# LPCB279_-_AND_GATES.net
KiCad netlist of a schematic drawn in Altium Designer
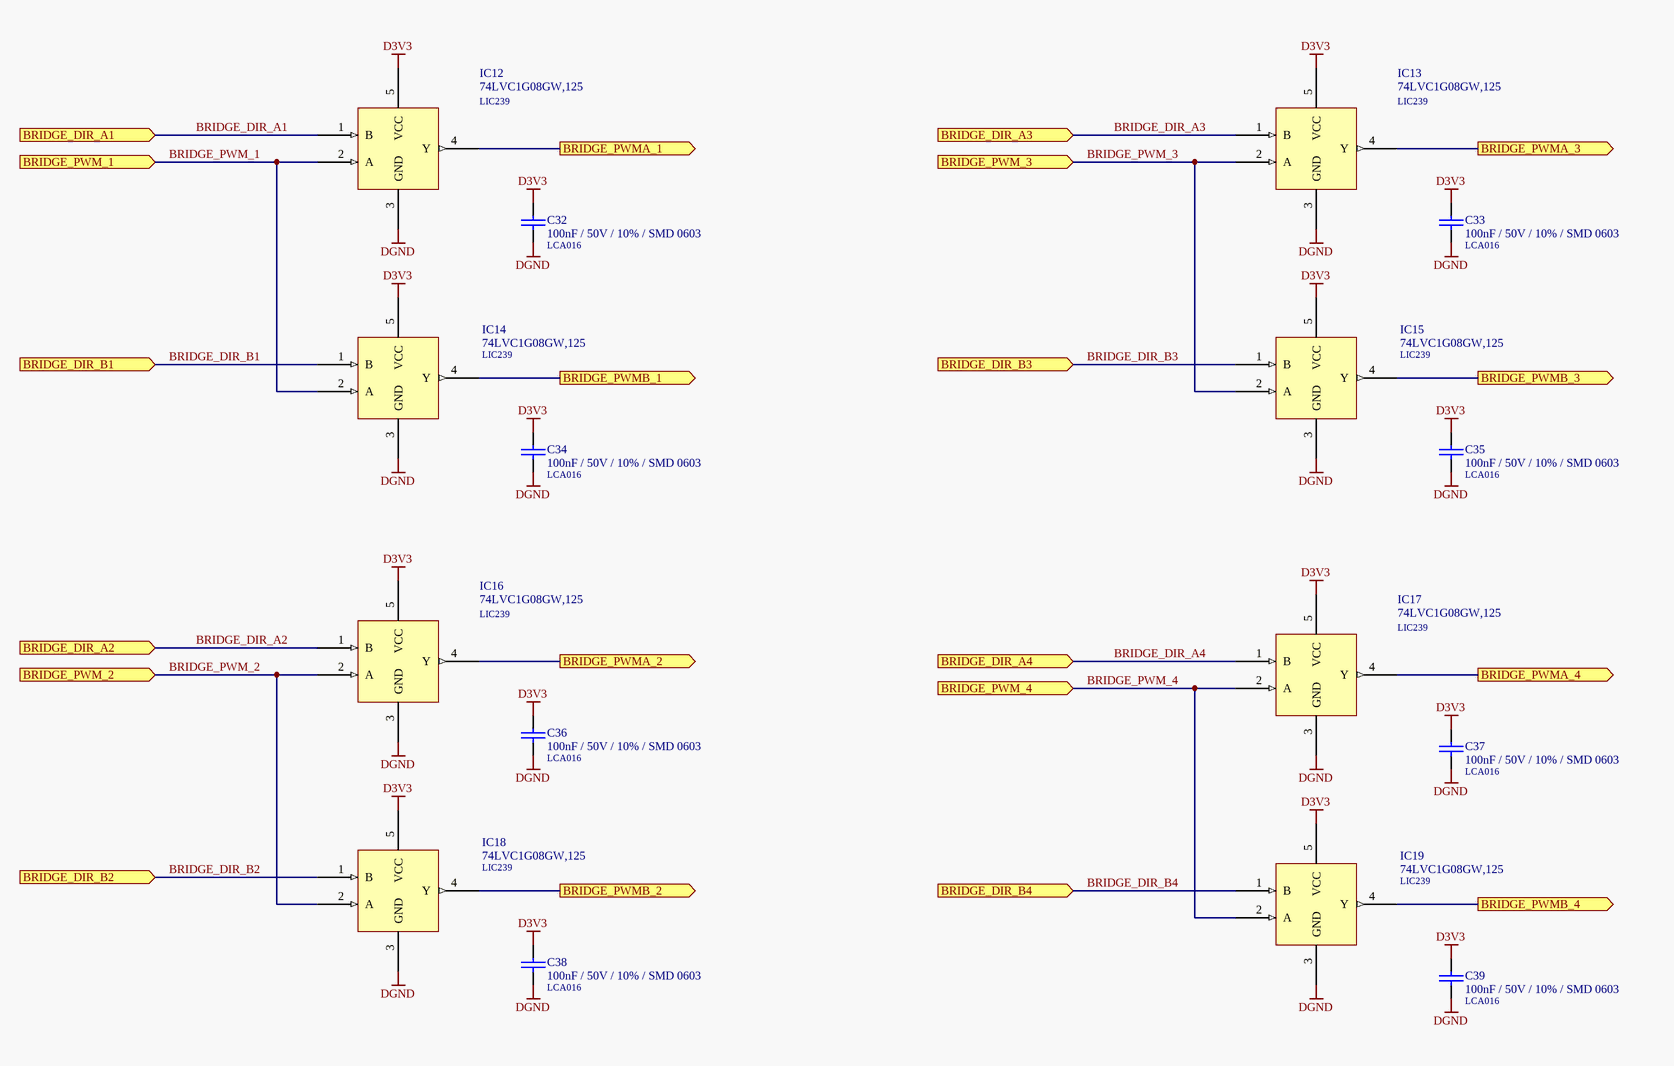
[diagram p0: LPCB279 - AND GATES.SchDoc]

(export (version "E")
  (design (tool "Eeschema 10.0.6"))
  (components
    (comp (ref "C32")
      (value "100nF / 50V / 10% / SMD 0603")
      (footprint "LFP011__CC1608-0603-IPC7351_B")
      (description "Capacitor, Ceramic Chip, 100nF (0.1uF), 50V, 5%, SMD 0603 [LCA016]")
      (fields (field (name "LDL_NUMBER") "LCA016"))
      (libsource (lib "LDL_Capacitors") (part "100nF / 50V / 10% / SMD 0603"))
    )
    (comp (ref "C33")
      (value "100nF / 50V / 10% / SMD 0603")
      (footprint "LFP011__CC1608-0603-IPC7351_B")
      (description "Capacitor, Ceramic Chip, 100nF (0.1uF), 50V, 5%, SMD 0603 [LCA016]")
      (fields (field (name "LDL_NUMBER") "LCA016"))
      (libsource (lib "LDL_Capacitors") (part "100nF / 50V / 10% / SMD 0603"))
    )
    (comp (ref "C34")
      (value "100nF / 50V / 10% / SMD 0603")
      (footprint "LFP011__CC1608-0603-IPC7351_B")
      (description "Capacitor, Ceramic Chip, 100nF (0.1uF), 50V, 5%, SMD 0603 [LCA016]")
      (fields (field (name "LDL_NUMBER") "LCA016"))
      (libsource (lib "LDL_Capacitors") (part "100nF / 50V / 10% / SMD 0603"))
    )
    (comp (ref "C35")
      (value "100nF / 50V / 10% / SMD 0603")
      (footprint "LFP011__CC1608-0603-IPC7351_B")
      (description "Capacitor, Ceramic Chip, 100nF (0.1uF), 50V, 5%, SMD 0603 [LCA016]")
      (fields (field (name "LDL_NUMBER") "LCA016"))
      (libsource (lib "LDL_Capacitors") (part "100nF / 50V / 10% / SMD 0603"))
    )
    (comp (ref "C36")
      (value "100nF / 50V / 10% / SMD 0603")
      (footprint "LFP011__CC1608-0603-IPC7351_B")
      (description "Capacitor, Ceramic Chip, 100nF (0.1uF), 50V, 5%, SMD 0603 [LCA016]")
      (fields (field (name "LDL_NUMBER") "LCA016"))
      (libsource (lib "LDL_Capacitors") (part "100nF / 50V / 10% / SMD 0603"))
    )
    (comp (ref "C37")
      (value "100nF / 50V / 10% / SMD 0603")
      (footprint "LFP011__CC1608-0603-IPC7351_B")
      (description "Capacitor, Ceramic Chip, 100nF (0.1uF), 50V, 5%, SMD 0603 [LCA016]")
      (fields (field (name "LDL_NUMBER") "LCA016"))
      (libsource (lib "LDL_Capacitors") (part "100nF / 50V / 10% / SMD 0603"))
    )
    (comp (ref "C38")
      (value "100nF / 50V / 10% / SMD 0603")
      (footprint "LFP011__CC1608-0603-IPC7351_B")
      (description "Capacitor, Ceramic Chip, 100nF (0.1uF), 50V, 5%, SMD 0603 [LCA016]")
      (fields (field (name "LDL_NUMBER") "LCA016"))
      (libsource (lib "LDL_Capacitors") (part "100nF / 50V / 10% / SMD 0603"))
    )
    (comp (ref "C39")
      (value "100nF / 50V / 10% / SMD 0603")
      (footprint "LFP011__CC1608-0603-IPC7351_B")
      (description "Capacitor, Ceramic Chip, 100nF (0.1uF), 50V, 5%, SMD 0603 [LCA016]")
      (fields (field (name "LDL_NUMBER") "LCA016"))
      (libsource (lib "LDL_Capacitors") (part "100nF / 50V / 10% / SMD 0603"))
    )
    (comp (ref "IC12")
      (value "74LVC1G08GW,125")
      (footprint "LFP047__SOT353")
      (description "IC, Logic AND Gate, Single 2 Input, SMD SOT353 [LIC239]")
      (fields (field (name "LDL_NUMBER") "LIC239"))
      (libsource (lib "LDL_Semiconductors") (part "74LVC1G08GW,125"))
    )
    (comp (ref "IC13")
      (value "74LVC1G08GW,125")
      (footprint "LFP047__SOT353")
      (description "IC, Logic AND Gate, Single 2 Input, SMD SOT353 [LIC239]")
      (fields (field (name "LDL_NUMBER") "LIC239"))
      (libsource (lib "LDL_Semiconductors") (part "74LVC1G08GW,125"))
    )
    (comp (ref "IC14")
      (value "74LVC1G08GW,125")
      (footprint "LFP047__SOT353")
      (description "IC, Logic AND Gate, Single 2 Input, SMD SOT353 [LIC239]")
      (fields (field (name "LDL_NUMBER") "LIC239"))
      (libsource (lib "LDL_Semiconductors") (part "74LVC1G08GW,125"))
    )
    (comp (ref "IC15")
      (value "74LVC1G08GW,125")
      (footprint "LFP047__SOT353")
      (description "IC, Logic AND Gate, Single 2 Input, SMD SOT353 [LIC239]")
      (fields (field (name "LDL_NUMBER") "LIC239"))
      (libsource (lib "LDL_Semiconductors") (part "74LVC1G08GW,125"))
    )
    (comp (ref "IC16")
      (value "74LVC1G08GW,125")
      (footprint "LFP047__SOT353")
      (description "IC, Logic AND Gate, Single 2 Input, SMD SOT353 [LIC239]")
      (fields (field (name "LDL_NUMBER") "LIC239"))
      (libsource (lib "LDL_Semiconductors") (part "74LVC1G08GW,125"))
    )
    (comp (ref "IC17")
      (value "74LVC1G08GW,125")
      (footprint "LFP047__SOT353")
      (description "IC, Logic AND Gate, Single 2 Input, SMD SOT353 [LIC239]")
      (fields (field (name "LDL_NUMBER") "LIC239"))
      (libsource (lib "LDL_Semiconductors") (part "74LVC1G08GW,125"))
    )
    (comp (ref "IC18")
      (value "74LVC1G08GW,125")
      (footprint "LFP047__SOT353")
      (description "IC, Logic AND Gate, Single 2 Input, SMD SOT353 [LIC239]")
      (fields (field (name "LDL_NUMBER") "LIC239"))
      (libsource (lib "LDL_Semiconductors") (part "74LVC1G08GW,125"))
    )
    (comp (ref "IC19")
      (value "74LVC1G08GW,125")
      (footprint "LFP047__SOT353")
      (description "IC, Logic AND Gate, Single 2 Input, SMD SOT353 [LIC239]")
      (fields (field (name "LDL_NUMBER") "LIC239"))
      (libsource (lib "LDL_Semiconductors") (part "74LVC1G08GW,125"))
    )
  )
  (nets
    (net (code "1") (name "/BRIDGE_DIR_A1") (class "Default")
      (node (ref "IC12") (pin "1") (pinfunction "B_1") (pintype "input"))
    )
    (net (code "2") (name "/BRIDGE_DIR_A2") (class "Default")
      (node (ref "IC16") (pin "1") (pinfunction "B_1") (pintype "input"))
    )
    (net (code "3") (name "/BRIDGE_DIR_A3") (class "Default")
      (node (ref "IC13") (pin "1") (pinfunction "B_1") (pintype "input"))
    )
    (net (code "4") (name "/BRIDGE_DIR_A4") (class "Default")
      (node (ref "IC17") (pin "1") (pinfunction "B_1") (pintype "input"))
    )
    (net (code "5") (name "/BRIDGE_DIR_B1") (class "Default")
      (node (ref "IC14") (pin "1") (pinfunction "B_1") (pintype "input"))
    )
    (net (code "6") (name "/BRIDGE_DIR_B2") (class "Default")
      (node (ref "IC18") (pin "1") (pinfunction "B_1") (pintype "input"))
    )
    (net (code "7") (name "/BRIDGE_DIR_B3") (class "Default")
      (node (ref "IC15") (pin "1") (pinfunction "B_1") (pintype "input"))
    )
    (net (code "8") (name "/BRIDGE_DIR_B4") (class "Default")
      (node (ref "IC19") (pin "1") (pinfunction "B_1") (pintype "input"))
    )
    (net (code "9") (name "/BRIDGE_PWMA_1") (class "Default")
      (node (ref "IC12") (pin "4") (pinfunction "Y_4") (pintype "output"))
    )
    (net (code "10") (name "/BRIDGE_PWMA_2") (class "Default")
      (node (ref "IC16") (pin "4") (pinfunction "Y_4") (pintype "output"))
    )
    (net (code "11") (name "/BRIDGE_PWMA_3") (class "Default")
      (node (ref "IC13") (pin "4") (pinfunction "Y_4") (pintype "output"))
    )
    (net (code "12") (name "/BRIDGE_PWMA_4") (class "Default")
      (node (ref "IC17") (pin "4") (pinfunction "Y_4") (pintype "output"))
    )
    (net (code "13") (name "/BRIDGE_PWMB_1") (class "Default")
      (node (ref "IC14") (pin "4") (pinfunction "Y_4") (pintype "output"))
    )
    (net (code "14") (name "/BRIDGE_PWMB_2") (class "Default")
      (node (ref "IC18") (pin "4") (pinfunction "Y_4") (pintype "output"))
    )
    (net (code "15") (name "/BRIDGE_PWMB_3") (class "Default")
      (node (ref "IC15") (pin "4") (pinfunction "Y_4") (pintype "output"))
    )
    (net (code "16") (name "/BRIDGE_PWMB_4") (class "Default")
      (node (ref "IC19") (pin "4") (pinfunction "Y_4") (pintype "output"))
    )
    (net (code "17") (name "/BRIDGE_PWM_1") (class "Default")
      (node (ref "IC12") (pin "2") (pinfunction "A_2") (pintype "input"))
      (node (ref "IC14") (pin "2") (pinfunction "A_2") (pintype "input"))
    )
    (net (code "18") (name "/BRIDGE_PWM_2") (class "Default")
      (node (ref "IC16") (pin "2") (pinfunction "A_2") (pintype "input"))
      (node (ref "IC18") (pin "2") (pinfunction "A_2") (pintype "input"))
    )
    (net (code "19") (name "/BRIDGE_PWM_3") (class "Default")
      (node (ref "IC13") (pin "2") (pinfunction "A_2") (pintype "input"))
      (node (ref "IC15") (pin "2") (pinfunction "A_2") (pintype "input"))
    )
    (net (code "20") (name "/BRIDGE_PWM_4") (class "Default")
      (node (ref "IC17") (pin "2") (pinfunction "A_2") (pintype "input"))
      (node (ref "IC19") (pin "2") (pinfunction "A_2") (pintype "input"))
    )
    (net (code "21") (name "D3V3") (class "Default")
      (node (ref "C32") (pin "1") (pintype "passive"))
      (node (ref "C33") (pin "1") (pintype "passive"))
      (node (ref "C34") (pin "1") (pintype "passive"))
      (node (ref "C35") (pin "1") (pintype "passive"))
      (node (ref "C36") (pin "1") (pintype "passive"))
      (node (ref "C37") (pin "1") (pintype "passive"))
      (node (ref "C38") (pin "1") (pintype "passive"))
      (node (ref "C39") (pin "1") (pintype "passive"))
      (node (ref "IC12") (pin "5") (pinfunction "VCC_5") (pintype "power_in"))
      (node (ref "IC13") (pin "5") (pinfunction "VCC_5") (pintype "power_in"))
      (node (ref "IC14") (pin "5") (pinfunction "VCC_5") (pintype "power_in"))
      (node (ref "IC15") (pin "5") (pinfunction "VCC_5") (pintype "power_in"))
      (node (ref "IC16") (pin "5") (pinfunction "VCC_5") (pintype "power_in"))
      (node (ref "IC17") (pin "5") (pinfunction "VCC_5") (pintype "power_in"))
      (node (ref "IC18") (pin "5") (pinfunction "VCC_5") (pintype "power_in"))
      (node (ref "IC19") (pin "5") (pinfunction "VCC_5") (pintype "power_in"))
    )
    (net (code "22") (name "DGND") (class "Default")
      (node (ref "C32") (pin "2") (pintype "passive"))
      (node (ref "C33") (pin "2") (pintype "passive"))
      (node (ref "C34") (pin "2") (pintype "passive"))
      (node (ref "C35") (pin "2") (pintype "passive"))
      (node (ref "C36") (pin "2") (pintype "passive"))
      (node (ref "C37") (pin "2") (pintype "passive"))
      (node (ref "C38") (pin "2") (pintype "passive"))
      (node (ref "C39") (pin "2") (pintype "passive"))
      (node (ref "IC12") (pin "3") (pinfunction "GND_3") (pintype "power_in"))
      (node (ref "IC13") (pin "3") (pinfunction "GND_3") (pintype "power_in"))
      (node (ref "IC14") (pin "3") (pinfunction "GND_3") (pintype "power_in"))
      (node (ref "IC15") (pin "3") (pinfunction "GND_3") (pintype "power_in"))
      (node (ref "IC16") (pin "3") (pinfunction "GND_3") (pintype "power_in"))
      (node (ref "IC17") (pin "3") (pinfunction "GND_3") (pintype "power_in"))
      (node (ref "IC18") (pin "3") (pinfunction "GND_3") (pintype "power_in"))
      (node (ref "IC19") (pin "3") (pinfunction "GND_3") (pintype "power_in"))
    )
  )
)
